# Nordic_main.net
KiCad netlist of a schematic drawn in Altium Designer
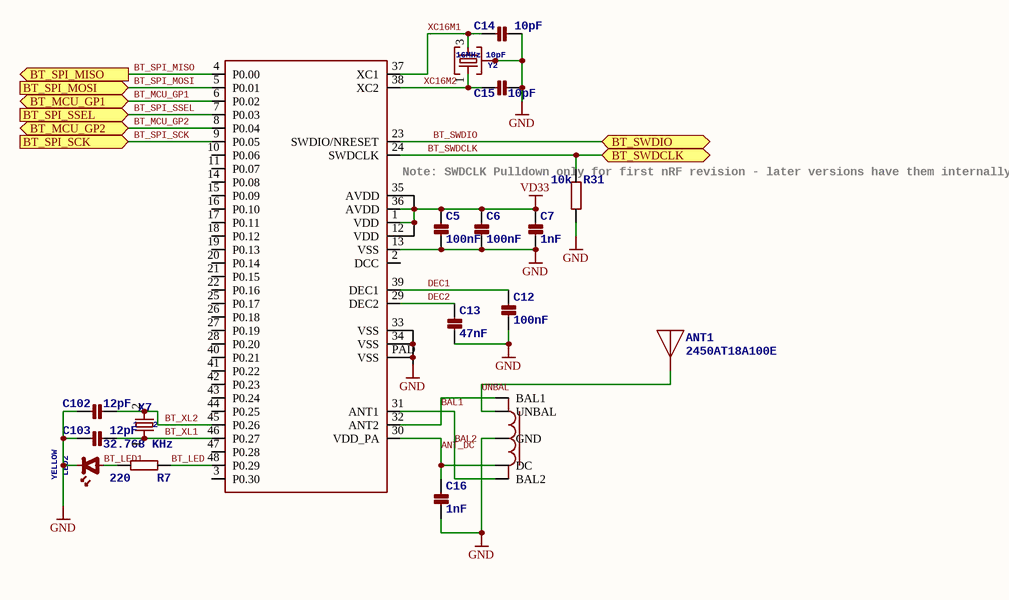
[diagram p0: Nordic_main.SchDoc]

(export (version "E")
  (design (tool "Eeschema 10.0.6"))
  (components
    (comp (ref "ANT1")
      (value "2450AT18A100E")
      (footprint "1206_MINIMELF_COMBO")
      (description "2.45 GHz Antenna")
      (libsource (lib "WunderBar_v101") (part "ANTENNA_MONOPOLE1206"))
    )
    (comp (ref "BALUN")
      (value "2450BM14A0002T")
      (footprint "6-PIN-0603")
      (description "2.45 GHz Impedance Matched Balun-Filter")
      (libsource (lib "WunderBar_v101") (part "BALUN"))
    )
    (comp (ref "BT")
      (value "NRF51822QFN48")
      (footprint "QFN48_EP")
      (description "Nordic Bluetooth 4.0 low energy modul")
      (libsource (lib "WunderBar_v101") (part "NRF51822QFN48"))
    )
    (comp (ref "C5")
      (value "100nF")
      (footprint "0402")
      (description "Ceramic Capacitor")
      (libsource (lib "WunderBar_v101") (part "CAP_CERAMIC0402"))
    )
    (comp (ref "C6")
      (value "100nF")
      (footprint "0402")
      (description "Ceramic Capacitor")
      (libsource (lib "WunderBar_v101") (part "CAP_CERAMIC0402"))
    )
    (comp (ref "C7")
      (value "1nF")
      (footprint "0402")
      (description "Ceramic Capacitor")
      (libsource (lib "WunderBar_v101") (part "CAP_CERAMIC0402"))
    )
    (comp (ref "C12")
      (value "100nF")
      (footprint "0402")
      (description "Ceramic Capacitor")
      (libsource (lib "WunderBar_v101") (part "CAP_CERAMIC0402"))
    )
    (comp (ref "C13")
      (value "47nF")
      (footprint "0402")
      (description "Ceramic Capacitor")
      (libsource (lib "WunderBar_v101") (part "CAP_CERAMIC0402"))
    )
    (comp (ref "C14")
      (value "10pF")
      (footprint "0402")
      (description "Ceramic Capacitor")
      (libsource (lib "") (part "CAP_CERAMIC0402_1"))
    )
    (comp (ref "C15")
      (value "10pF")
      (footprint "0402")
      (description "Ceramic Capacitor")
      (libsource (lib "") (part "CAP_CERAMIC0402_1"))
    )
    (comp (ref "C16")
      (value "1nF")
      (footprint "0402")
      (description "Ceramic Capacitor")
      (libsource (lib "WunderBar_v101") (part "CAP_CERAMIC0402"))
    )
    (comp (ref "C102")
      (value "12pF")
      (footprint "0402")
      (description "Ceramic Capacitor")
      (libsource (lib "") (part "CAP_CERAMIC0402_1"))
    )
    (comp (ref "C103")
      (value "12pF")
      (footprint "0402")
      (description "Ceramic Capacitor")
      (libsource (lib "") (part "CAP_CERAMIC0402_1"))
    )
    (comp (ref "LED2")
      (value "YELLOW")
      (footprint "0402_POLAR")
      (description "LED common")
      (libsource (lib "WunderBar_v101") (part "LED0402"))
    )
    (comp (ref "R7")
      (value "220")
      (footprint "0402")
      (description "RESISTOR")
      (libsource (lib "WunderBar_v101") (part "R-EU_0402"))
    )
    (comp (ref "R31")
      (value "10k")
      (footprint "0402")
      (description "RESISTOR")
      (libsource (lib "WunderBar_v101") (part "R-EU_0402"))
    )
    (comp (ref "X7")
      (value "32.768 KHz")
      (footprint "1206_MINIMELF_COMBO")
      (description "CL05C120JB5")
      (fields (field (name "1") "1") (field (name "2") "2"))
      (libsource (lib "WunderBar_v101") (part "CRYSTAL1206"))
    )
    (comp (ref "Y2")
      (value "16MHz 10pF")
      (footprint "CRYSTAL25X20")
      (description "16MHz crystal 2.5x2mm")
      (libsource (lib "WunderBar_v101") (part "CRYSTAL_WITH_GROUND25X20"))
    )
  )
  (nets
    (net (code "1") (name "/ANT_DC") (class "Default")
      (node (ref "BALUN") (pin "5") (pinfunction "DC_5") (pintype "power_in"))
      (node (ref "BT") (pin "30") (pinfunction "VDD_PA_30") (pintype "passive"))
      (node (ref "C16") (pin "1") (pinfunction "1_1") (pintype "passive"))
    )
    (net (code "2") (name "/BAL1") (class "Default")
      (node (ref "BALUN") (pin "3") (pinfunction "BAL1_3") (pintype "passive"))
      (node (ref "BT") (pin "32") (pinfunction "ANT2_32") (pintype "passive"))
    )
    (net (code "3") (name "/BAL2") (class "Default")
      (node (ref "BALUN") (pin "4") (pinfunction "BAL2_4") (pintype "passive"))
      (node (ref "BT") (pin "31") (pinfunction "ANT1_31") (pintype "passive"))
    )
    (net (code "4") (name "/BT_LED") (class "Default")
      (node (ref "BT") (pin "48") (pinfunction "P0.29_48") (pintype "passive"))
      (node (ref "R7") (pin "1") (pinfunction "1_1") (pintype "passive"))
    )
    (net (code "5") (name "/BT_LED1") (class "Default")
      (node (ref "LED2") (pin "A") (pinfunction "ANODE_A") (pintype "passive"))
      (node (ref "R7") (pin "2") (pinfunction "2_2") (pintype "passive"))
    )
    (net (code "6") (name "/BT_MCU_GP1") (class "Default")
      (node (ref "BT") (pin "6") (pinfunction "P0.02_6") (pintype "passive"))
    )
    (net (code "7") (name "/BT_MCU_GP2") (class "Default")
      (node (ref "BT") (pin "8") (pinfunction "P0.04_8") (pintype "passive"))
    )
    (net (code "8") (name "/BT_SPI_MISO") (class "Default")
      (node (ref "BT") (pin "4") (pinfunction "P0.00_4") (pintype "passive"))
    )
    (net (code "9") (name "/BT_SPI_MOSI") (class "Default")
      (node (ref "BT") (pin "5") (pinfunction "P0.01_5") (pintype "passive"))
    )
    (net (code "10") (name "/BT_SPI_SCK") (class "Default")
      (node (ref "BT") (pin "9") (pinfunction "P0.05_9") (pintype "passive"))
    )
    (net (code "11") (name "/BT_SPI_SSEL") (class "Default")
      (node (ref "BT") (pin "7") (pinfunction "P0.03_7") (pintype "passive"))
    )
    (net (code "12") (name "/BT_SWDCLK") (class "Default")
      (node (ref "BT") (pin "24") (pinfunction "SWDCLK_24") (pintype "passive"))
      (node (ref "R31") (pin "2") (pinfunction "2_2") (pintype "passive"))
    )
    (net (code "13") (name "/BT_SWDIO") (class "Default")
      (node (ref "BT") (pin "23") (pinfunction "SWDIO/NRESET_23") (pintype "passive"))
    )
    (net (code "14") (name "/BT_XL1") (class "Default")
      (node (ref "BT") (pin "46") (pinfunction "P0.27_46") (pintype "passive"))
      (node (ref "C103") (pin "2") (pinfunction "2_2") (pintype "passive"))
      (node (ref "X7") (pin "1") (pinfunction "1_1") (pintype "passive"))
    )
    (net (code "15") (name "/BT_XL2") (class "Default")
      (node (ref "BT") (pin "45") (pinfunction "P0.26_45") (pintype "passive"))
      (node (ref "C102") (pin "2") (pinfunction "2_2") (pintype "passive"))
      (node (ref "X7") (pin "2") (pinfunction "2_2") (pintype "passive"))
    )
    (net (code "16") (name "/DEC1") (class "Default")
      (node (ref "BT") (pin "39") (pinfunction "DEC1_39") (pintype "passive"))
      (node (ref "C12") (pin "1") (pinfunction "1_1") (pintype "passive"))
    )
    (net (code "17") (name "/DEC2") (class "Default")
      (node (ref "BT") (pin "29") (pinfunction "DEC2_29") (pintype "passive"))
      (node (ref "C13") (pin "1") (pinfunction "1_1") (pintype "passive"))
    )
    (net (code "18") (name "/UNBAL") (class "Default")
      (node (ref "ANT1") (pin "1") (pinfunction "ANT_1") (pintype "passive"))
      (node (ref "BALUN") (pin "1") (pinfunction "UNBAL_1") (pintype "passive"))
    )
    (net (code "19") (name "/XC16M1") (class "Default")
      (node (ref "BT") (pin "37") (pinfunction "XC1_37") (pintype "passive"))
      (node (ref "C14") (pin "1") (pinfunction "1_1") (pintype "passive"))
      (node (ref "Y2") (pin "3") (pinfunction "3_3") (pintype "passive"))
    )
    (net (code "20") (name "/XC16M2") (class "Default")
      (node (ref "BT") (pin "38") (pinfunction "XC2_38") (pintype "passive"))
      (node (ref "C15") (pin "1") (pinfunction "1_1") (pintype "passive"))
      (node (ref "Y2") (pin "1") (pinfunction "1_1") (pintype "passive"))
    )
    (net (code "21") (name "GND") (class "Default")
      (node (ref "BALUN") (pin "2") (pinfunction "GND_2") (pintype "power_in"))
      (node (ref "BT") (pin "13") (pinfunction "VSS_13") (pintype "passive"))
      (node (ref "BT") (pin "33") (pinfunction "VSS_33") (pintype "passive"))
      (node (ref "BT") (pin "34") (pinfunction "VSS_34") (pintype "passive"))
      (node (ref "BT") (pin "PAD") (pinfunction "VSS_PAD") (pintype "passive"))
      (node (ref "C102") (pin "1") (pinfunction "1_1") (pintype "passive"))
      (node (ref "C103") (pin "1") (pinfunction "1_1") (pintype "passive"))
      (node (ref "C12") (pin "2") (pinfunction "2_2") (pintype "passive"))
      (node (ref "C13") (pin "2") (pinfunction "2_2") (pintype "passive"))
      (node (ref "C14") (pin "2") (pinfunction "2_2") (pintype "passive"))
      (node (ref "C15") (pin "2") (pinfunction "2_2") (pintype "passive"))
      (node (ref "C16") (pin "2") (pinfunction "2_2") (pintype "passive"))
      (node (ref "C5") (pin "2") (pinfunction "2_2") (pintype "passive"))
      (node (ref "C6") (pin "2") (pinfunction "2_2") (pintype "passive"))
      (node (ref "C7") (pin "2") (pinfunction "2_2") (pintype "passive"))
      (node (ref "LED2") (pin "K") (pinfunction "CATHODE_K") (pintype "passive"))
      (node (ref "R31") (pin "1") (pinfunction "1_1") (pintype "passive"))
      (node (ref "Y2") (pin "2") (pinfunction "2_2") (pintype "power_in"))
      (node (ref "Y2") (pin "4") (pinfunction "4_4") (pintype "power_in"))
    )
    (net (code "22") (name "VD33") (class "Default")
      (node (ref "BT") (pin "1") (pinfunction "VDD_1") (pintype "passive"))
      (node (ref "BT") (pin "12") (pinfunction "VDD_12") (pintype "passive"))
      (node (ref "BT") (pin "35") (pinfunction "AVDD_35") (pintype "passive"))
      (node (ref "BT") (pin "36") (pinfunction "AVDD_36") (pintype "passive"))
      (node (ref "C5") (pin "1") (pinfunction "1_1") (pintype "passive"))
      (node (ref "C6") (pin "1") (pinfunction "1_1") (pintype "passive"))
      (node (ref "C7") (pin "1") (pinfunction "1_1") (pintype "passive"))
    )
    (net (code "23") (name "unconnected-(BT-DCC-Pad2)") (class "Default")
      (node (ref "BT") (pin "2") (pinfunction "DCC_2") (pintype "passive"))
    )
    (net (code "24") (name "unconnected-(BT-P0.06-Pad10)") (class "Default")
      (node (ref "BT") (pin "10") (pinfunction "P0.06_10") (pintype "passive"))
    )
    (net (code "25") (name "unconnected-(BT-P0.07-Pad11)") (class "Default")
      (node (ref "BT") (pin "11") (pinfunction "P0.07_11") (pintype "passive"))
    )
    (net (code "26") (name "unconnected-(BT-P0.08-Pad14)") (class "Default")
      (node (ref "BT") (pin "14") (pinfunction "P0.08_14") (pintype "passive"))
    )
    (net (code "27") (name "unconnected-(BT-P0.09-Pad15)") (class "Default")
      (node (ref "BT") (pin "15") (pinfunction "P0.09_15") (pintype "passive"))
    )
    (net (code "28") (name "unconnected-(BT-P0.10-Pad16)") (class "Default")
      (node (ref "BT") (pin "16") (pinfunction "P0.10_16") (pintype "passive"))
    )
    (net (code "29") (name "unconnected-(BT-P0.11-Pad17)") (class "Default")
      (node (ref "BT") (pin "17") (pinfunction "P0.11_17") (pintype "passive"))
    )
    (net (code "30") (name "unconnected-(BT-P0.12-Pad18)") (class "Default")
      (node (ref "BT") (pin "18") (pinfunction "P0.12_18") (pintype "passive"))
    )
    (net (code "31") (name "unconnected-(BT-P0.13-Pad19)") (class "Default")
      (node (ref "BT") (pin "19") (pinfunction "P0.13_19") (pintype "passive"))
    )
    (net (code "32") (name "unconnected-(BT-P0.14-Pad20)") (class "Default")
      (node (ref "BT") (pin "20") (pinfunction "P0.14_20") (pintype "passive"))
    )
    (net (code "33") (name "unconnected-(BT-P0.15-Pad21)") (class "Default")
      (node (ref "BT") (pin "21") (pinfunction "P0.15_21") (pintype "passive"))
    )
    (net (code "34") (name "unconnected-(BT-P0.16-Pad22)") (class "Default")
      (node (ref "BT") (pin "22") (pinfunction "P0.16_22") (pintype "passive"))
    )
    (net (code "35") (name "unconnected-(BT-P0.17-Pad25)") (class "Default")
      (node (ref "BT") (pin "25") (pinfunction "P0.17_25") (pintype "passive"))
    )
    (net (code "36") (name "unconnected-(BT-P0.18-Pad26)") (class "Default")
      (node (ref "BT") (pin "26") (pinfunction "P0.18_26") (pintype "passive"))
    )
    (net (code "37") (name "unconnected-(BT-P0.19-Pad27)") (class "Default")
      (node (ref "BT") (pin "27") (pinfunction "P0.19_27") (pintype "passive"))
    )
    (net (code "38") (name "unconnected-(BT-P0.20-Pad28)") (class "Default")
      (node (ref "BT") (pin "28") (pinfunction "P0.20_28") (pintype "passive"))
    )
    (net (code "39") (name "unconnected-(BT-P0.21-Pad40)") (class "Default")
      (node (ref "BT") (pin "40") (pinfunction "P0.21_40") (pintype "passive"))
    )
    (net (code "40") (name "unconnected-(BT-P0.22-Pad41)") (class "Default")
      (node (ref "BT") (pin "41") (pinfunction "P0.22_41") (pintype "passive"))
    )
    (net (code "41") (name "unconnected-(BT-P0.23-Pad42)") (class "Default")
      (node (ref "BT") (pin "42") (pinfunction "P0.23_42") (pintype "passive"))
    )
    (net (code "42") (name "unconnected-(BT-P0.24-Pad43)") (class "Default")
      (node (ref "BT") (pin "43") (pinfunction "P0.24_43") (pintype "passive"))
    )
    (net (code "43") (name "unconnected-(BT-P0.25-Pad44)") (class "Default")
      (node (ref "BT") (pin "44") (pinfunction "P0.25_44") (pintype "passive"))
    )
    (net (code "44") (name "unconnected-(BT-P0.28-Pad47)") (class "Default")
      (node (ref "BT") (pin "47") (pinfunction "P0.28_47") (pintype "passive"))
    )
    (net (code "45") (name "unconnected-(BT-P0.30-Pad3)") (class "Default")
      (node (ref "BT") (pin "3") (pinfunction "P0.30_3") (pintype "passive"))
    )
  )
)
